# power.net
KiCad netlist of a schematic drawn in EAGLE
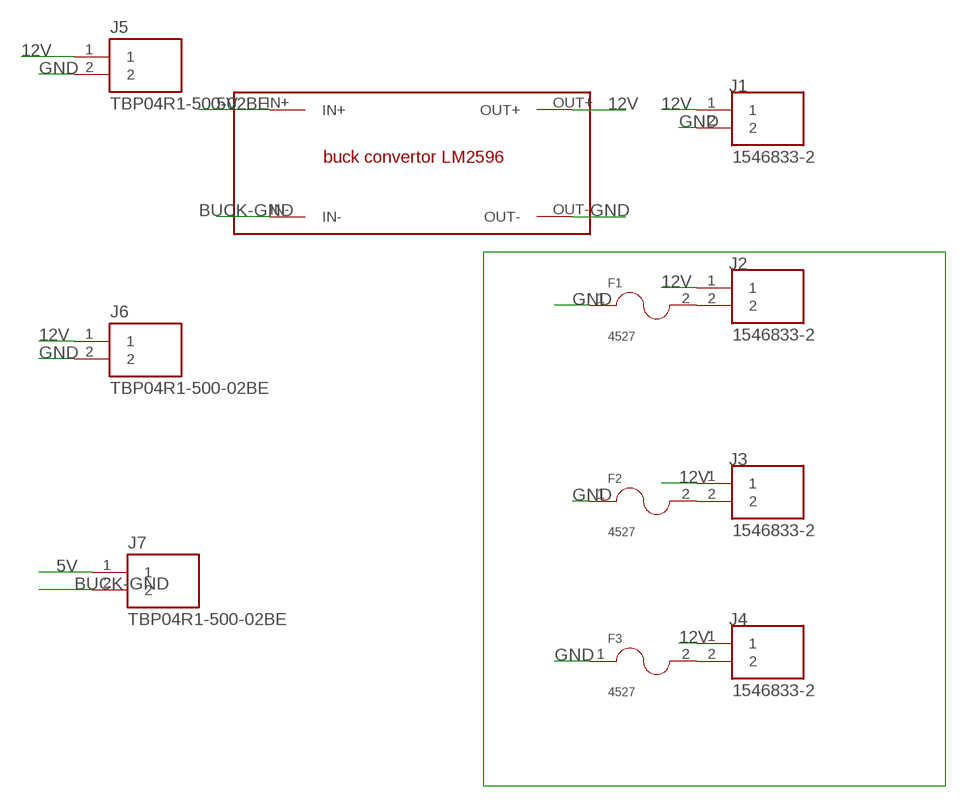
[diagram p0: schematic, sheet 1]

(export (version "E")
  (design (tool "Eeschema 10.0.6"))
  (components
    (comp (ref "F1")
      (value "4527")
      (footprint "eagle-import:FUSE_4527")
      (fields (field (name "MF") "Keystone"))
      (libsource (lib "eagle-import") (part "4527"))
    )
    (comp (ref "F2")
      (value "4527")
      (footprint "eagle-import:FUSE_4527")
      (fields (field (name "MF") "Keystone"))
      (libsource (lib "eagle-import") (part "4527"))
    )
    (comp (ref "F3")
      (value "4527")
      (footprint "eagle-import:FUSE_4527")
      (fields (field (name "MF") "Keystone"))
      (libsource (lib "eagle-import") (part "4527"))
    )
    (comp (ref "J1")
      (value "1546833-2")
      (footprint "eagle-import:TE_1546833-2")
      (fields (field (name "MF") "TE Connectivity"))
      (libsource (lib "eagle-import") (part "1546833-2"))
    )
    (comp (ref "J2")
      (value "1546833-2")
      (footprint "eagle-import:TE_1546833-2")
      (fields (field (name "MF") "TE Connectivity"))
      (libsource (lib "eagle-import") (part "1546833-2"))
    )
    (comp (ref "J3")
      (value "1546833-2")
      (footprint "eagle-import:TE_1546833-2")
      (fields (field (name "MF") "TE Connectivity"))
      (libsource (lib "eagle-import") (part "1546833-2"))
    )
    (comp (ref "J4")
      (value "1546833-2")
      (footprint "eagle-import:TE_1546833-2")
      (fields (field (name "MF") "TE Connectivity"))
      (libsource (lib "eagle-import") (part "1546833-2"))
    )
    (comp (ref "J5")
      (value "TBP04R1-500-02BE")
      (footprint "eagle-import:CUI_TBP04R1-500-02BE")
      (fields (field (name "MF") "Same Sky"))
      (libsource (lib "eagle-import") (part "TBP04R1-500-02BE"))
    )
    (comp (ref "J6")
      (value "TBP04R1-500-02BE")
      (footprint "eagle-import:CUI_TBP04R1-500-02BE")
      (fields (field (name "MF") "Same Sky"))
      (libsource (lib "eagle-import") (part "TBP04R1-500-02BE"))
    )
    (comp (ref "J7")
      (value "TBP04R1-500-02BE")
      (footprint "eagle-import:CUI_TBP04R1-500-02BE")
      (fields (field (name "MF") "Same Sky"))
      (libsource (lib "eagle-import") (part "TBP04R1-500-02BE"))
    )
    (comp (ref "U$1")
      (value "LM2596")
      (footprint "eagle-import:LM2596")
      (libsource (lib "eagle-import") (part "LM2596"))
    )
  )
  (nets
    (net (code "1") (name "/5V") (class "Default")
      (node (ref "J7") (pin "1") (pinfunction "1_1") (pintype "passive"))
      (node (ref "U$1") (pin "IN+") (pinfunction "IN+_IN+") (pintype "bidirectional"))
    )
    (net (code "2") (name "/12V") (class "Default")
      (node (ref "J1") (pin "1") (pinfunction "1_1") (pintype "passive"))
      (node (ref "J2") (pin "1") (pinfunction "1_1") (pintype "passive"))
      (node (ref "J3") (pin "1") (pinfunction "1_1") (pintype "passive"))
      (node (ref "J4") (pin "1") (pinfunction "1_1") (pintype "passive"))
      (node (ref "J5") (pin "1") (pinfunction "1_1") (pintype "passive"))
      (node (ref "J6") (pin "1") (pinfunction "1_1") (pintype "passive"))
      (node (ref "U$1") (pin "OUT+") (pinfunction "OUT+_OUT+") (pintype "bidirectional"))
    )
    (net (code "3") (name "/BUCK-GND") (class "Default")
      (node (ref "J7") (pin "2") (pinfunction "2_2") (pintype "passive"))
      (node (ref "U$1") (pin "IN-") (pinfunction "IN-_IN-") (pintype "bidirectional"))
    )
    (net (code "4") (name "/GND") (class "Default")
      (node (ref "F1") (pin "1") (pinfunction "1_1") (pintype "passive"))
      (node (ref "F2") (pin "1") (pinfunction "1_1") (pintype "passive"))
      (node (ref "F3") (pin "1") (pinfunction "1_1") (pintype "passive"))
      (node (ref "J1") (pin "2") (pinfunction "2_2") (pintype "passive"))
      (node (ref "J5") (pin "2") (pinfunction "2_2") (pintype "passive"))
      (node (ref "J6") (pin "2") (pinfunction "2_2") (pintype "passive"))
      (node (ref "U$1") (pin "OUT-") (pinfunction "OUT-_OUT-") (pintype "bidirectional"))
    )
    (net (code "5") (name "Net-(F1-Pad2)") (class "Default")
      (node (ref "F1") (pin "2") (pinfunction "2_2") (pintype "passive"))
      (node (ref "J2") (pin "2") (pinfunction "2_2") (pintype "passive"))
    )
    (net (code "6") (name "Net-(F2-Pad2)") (class "Default")
      (node (ref "F2") (pin "2") (pinfunction "2_2") (pintype "passive"))
      (node (ref "J3") (pin "2") (pinfunction "2_2") (pintype "passive"))
    )
    (net (code "7") (name "Net-(F3-Pad2)") (class "Default")
      (node (ref "F3") (pin "2") (pinfunction "2_2") (pintype "passive"))
      (node (ref "J4") (pin "2") (pinfunction "2_2") (pintype "passive"))
    )
  )
)
